# SOFTWEAR_microbit2.net
KiCad netlist of a schematic drawn in EAGLE
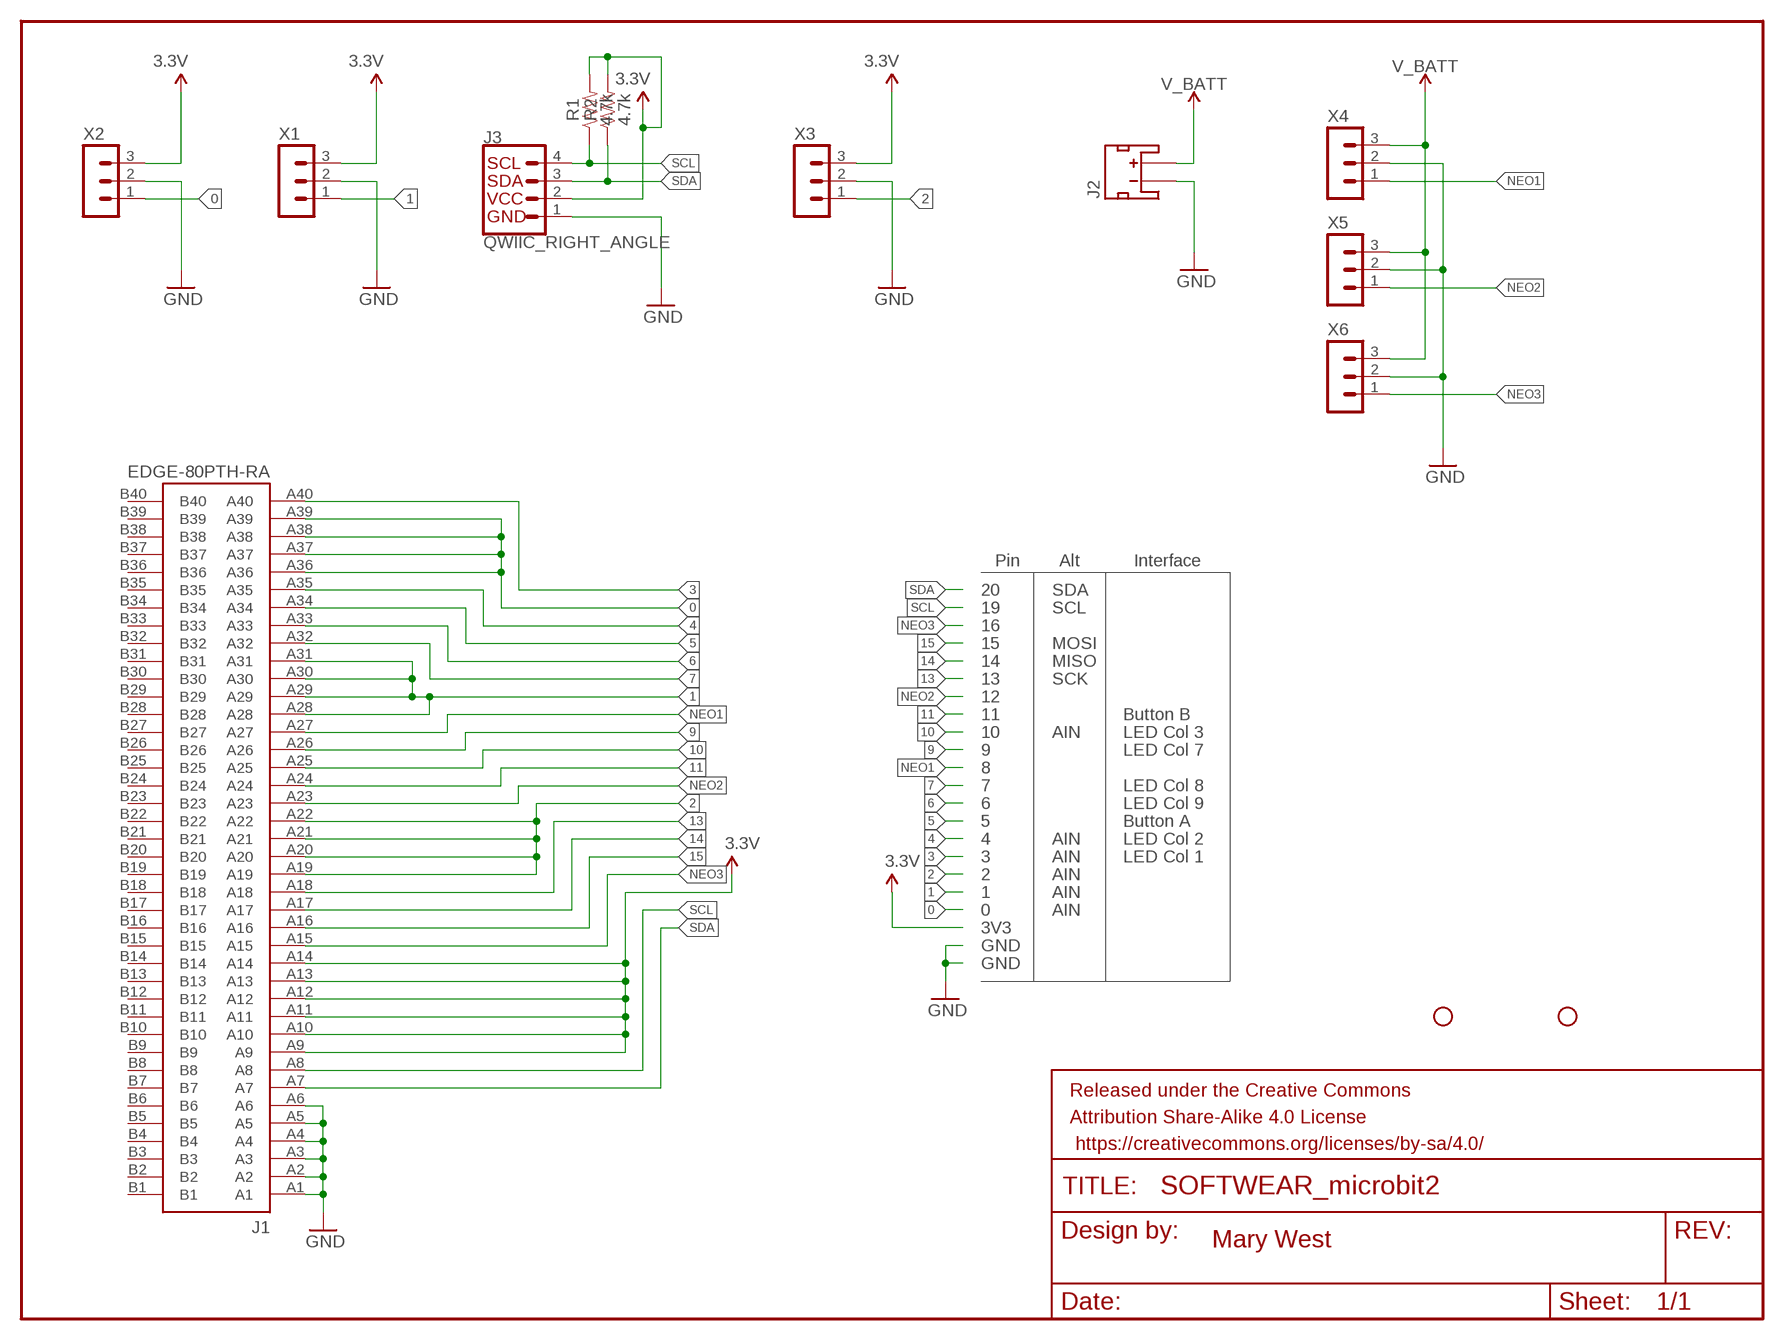
[diagram p0: schematic, sheet 1]

(export (version "E")
  (design (tool "Eeschema 10.0.6"))
  (components
    (comp (ref "FRAME2")
      (value "FRAME-LETTERNO_PACKAGE")
      (footprint "eagle-import:DUMMY")
      (fields (field (name "DESIGNER") "Nobody"))
      (libsource (lib "eagle-import") (part "FRAME-LETTERNO_PACKAGE"))
    )
    (comp (ref "H1")
      (value "STAND-OFF")
      (footprint "eagle-import:STAND-OFF")
      (libsource (lib "eagle-import") (part "STAND-OFF"))
    )
    (comp (ref "H2")
      (value "STAND-OFF")
      (footprint "eagle-import:STAND-OFF")
      (libsource (lib "eagle-import") (part "STAND-OFF"))
    )
    (comp (ref "J1")
      (value "EDGE-80PTH-RA")
      (footprint "eagle-import:VEC-127-080-R")
      (libsource (lib "eagle-import") (part "EDGE-80PTH-RA"))
    )
    (comp (ref "J2")
      (value "JST_2MM_MALE")
      (footprint "eagle-import:JST-2-SMD")
      (libsource (lib "eagle-import") (part "JST_2MM_MALE"))
    )
    (comp (ref "J3")
      (value "QWIIC_RIGHT_ANGLE")
      (footprint "eagle-import:JST04_1MM_RA")
      (libsource (lib "eagle-import") (part "QWIIC_CONNECTORJS-1MM"))
    )
    (comp (ref "R1")
      (value "4.7k")
      (footprint "eagle-import:0603")
      (libsource (lib "eagle-import") (part "4.7KOHM-0603-1/10W-1%"))
    )
    (comp (ref "R2")
      (value "4.7k")
      (footprint "eagle-import:0603")
      (libsource (lib "eagle-import") (part "4.7KOHM-0603-1/10W-1%"))
    )
    (comp (ref "X1")
      (value "SM03B-SRSS-TB")
      (footprint "eagle-import:SM03B-SRSS-TB")
      (libsource (lib "eagle-import") (part "SM03B-SRSS-TB"))
    )
    (comp (ref "X2")
      (value "SM03B-SRSS-TB")
      (footprint "eagle-import:SM03B-SRSS-TB")
      (libsource (lib "eagle-import") (part "SM03B-SRSS-TB"))
    )
    (comp (ref "X3")
      (value "SM03B-SRSS-TB")
      (footprint "eagle-import:SM03B-SRSS-TB")
      (libsource (lib "eagle-import") (part "SM03B-SRSS-TB"))
    )
    (comp (ref "X4")
      (value "SM03B-SRSS-TB")
      (footprint "eagle-import:SM03B-SRSS-TB")
      (libsource (lib "eagle-import") (part "SM03B-SRSS-TB"))
    )
    (comp (ref "X5")
      (value "SM03B-SRSS-TB")
      (footprint "eagle-import:SM03B-SRSS-TB")
      (libsource (lib "eagle-import") (part "SM03B-SRSS-TB"))
    )
    (comp (ref "X6")
      (value "SM03B-SRSS-TB")
      (footprint "eagle-import:SM03B-SRSS-TB")
      (libsource (lib "eagle-import") (part "SM03B-SRSS-TB"))
    )
  )
  (nets
    (net (code "1") (name "0") (class "Default")
      (node (ref "J1") (pin "A36") (pinfunction "A36_A36") (pintype "bidirectional"))
      (node (ref "J1") (pin "A37") (pinfunction "A37_A37") (pintype "bidirectional"))
      (node (ref "J1") (pin "A38") (pinfunction "A38_A38") (pintype "bidirectional"))
      (node (ref "J1") (pin "A39") (pinfunction "A39_A39") (pintype "bidirectional"))
      (node (ref "X2") (pin "1") (pinfunction "1_1") (pintype "passive"))
    )
    (net (code "2") (name "1") (class "Default")
      (node (ref "J1") (pin "A28") (pinfunction "A28_A28") (pintype "bidirectional"))
      (node (ref "J1") (pin "A29") (pinfunction "A29_A29") (pintype "bidirectional"))
      (node (ref "J1") (pin "A30") (pinfunction "A30_A30") (pintype "bidirectional"))
      (node (ref "J1") (pin "A31") (pinfunction "A31_A31") (pintype "bidirectional"))
      (node (ref "X1") (pin "1") (pinfunction "1_1") (pintype "passive"))
    )
    (net (code "3") (name "2") (class "Default")
      (node (ref "J1") (pin "A19") (pinfunction "A19_A19") (pintype "bidirectional"))
      (node (ref "J1") (pin "A20") (pinfunction "A20_A20") (pintype "bidirectional"))
      (node (ref "J1") (pin "A21") (pinfunction "A21_A21") (pintype "bidirectional"))
      (node (ref "J1") (pin "A22") (pinfunction "A22_A22") (pintype "bidirectional"))
      (node (ref "X3") (pin "1") (pinfunction "1_1") (pintype "passive"))
    )
    (net (code "4") (name "3") (class "Default")
      (node (ref "J1") (pin "A40") (pinfunction "A40_A40") (pintype "bidirectional"))
    )
    (net (code "5") (name "3.3V") (class "Default")
      (node (ref "J1") (pin "A10") (pinfunction "A10_A10") (pintype "bidirectional"))
      (node (ref "J1") (pin "A11") (pinfunction "A11_A11") (pintype "bidirectional"))
      (node (ref "J1") (pin "A12") (pinfunction "A12_A12") (pintype "bidirectional"))
      (node (ref "J1") (pin "A13") (pinfunction "A13_A13") (pintype "bidirectional"))
      (node (ref "J1") (pin "A14") (pinfunction "A14_A14") (pintype "bidirectional"))
      (node (ref "J1") (pin "A9") (pinfunction "A9_A9") (pintype "bidirectional"))
      (node (ref "J3") (pin "2") (pinfunction "2_2") (pintype "power_in"))
      (node (ref "R1") (pin "2") (pinfunction "2_2") (pintype "passive"))
      (node (ref "R2") (pin "2") (pinfunction "2_2") (pintype "passive"))
      (node (ref "X1") (pin "3") (pinfunction "3_3") (pintype "passive"))
      (node (ref "X2") (pin "3") (pinfunction "3_3") (pintype "passive"))
      (node (ref "X3") (pin "3") (pinfunction "3_3") (pintype "passive"))
    )
    (net (code "6") (name "4") (class "Default")
      (node (ref "J1") (pin "A35") (pinfunction "A35_A35") (pintype "bidirectional"))
    )
    (net (code "7") (name "5") (class "Default")
      (node (ref "J1") (pin "A34") (pinfunction "A34_A34") (pintype "bidirectional"))
    )
    (net (code "8") (name "6") (class "Default")
      (node (ref "J1") (pin "A33") (pinfunction "A33_A33") (pintype "bidirectional"))
    )
    (net (code "9") (name "7") (class "Default")
      (node (ref "J1") (pin "A32") (pinfunction "A32_A32") (pintype "bidirectional"))
    )
    (net (code "10") (name "9") (class "Default")
      (node (ref "J1") (pin "A26") (pinfunction "A26_A26") (pintype "bidirectional"))
    )
    (net (code "11") (name "10") (class "Default")
      (node (ref "J1") (pin "A25") (pinfunction "A25_A25") (pintype "bidirectional"))
    )
    (net (code "12") (name "11") (class "Default")
      (node (ref "J1") (pin "A24") (pinfunction "A24_A24") (pintype "bidirectional"))
    )
    (net (code "13") (name "13") (class "Default")
      (node (ref "J1") (pin "A18") (pinfunction "A18_A18") (pintype "bidirectional"))
    )
    (net (code "14") (name "14") (class "Default")
      (node (ref "J1") (pin "A17") (pinfunction "A17_A17") (pintype "bidirectional"))
    )
    (net (code "15") (name "15") (class "Default")
      (node (ref "J1") (pin "A16") (pinfunction "A16_A16") (pintype "bidirectional"))
    )
    (net (code "16") (name "GND") (class "Default")
      (node (ref "J1") (pin "A1") (pinfunction "A1_A1") (pintype "bidirectional"))
      (node (ref "J1") (pin "A2") (pinfunction "A2_A2") (pintype "bidirectional"))
      (node (ref "J1") (pin "A3") (pinfunction "A3_A3") (pintype "bidirectional"))
      (node (ref "J1") (pin "A4") (pinfunction "A4_A4") (pintype "bidirectional"))
      (node (ref "J1") (pin "A5") (pinfunction "A5_A5") (pintype "bidirectional"))
      (node (ref "J1") (pin "A6") (pinfunction "A6_A6") (pintype "bidirectional"))
      (node (ref "J2") (pin "1") (pinfunction "-_1") (pintype "bidirectional"))
      (node (ref "J3") (pin "1") (pinfunction "1_1") (pintype "power_in"))
      (node (ref "X1") (pin "2") (pinfunction "2_2") (pintype "passive"))
      (node (ref "X2") (pin "2") (pinfunction "2_2") (pintype "passive"))
      (node (ref "X3") (pin "2") (pinfunction "2_2") (pintype "passive"))
      (node (ref "X4") (pin "2") (pinfunction "2_2") (pintype "passive"))
      (node (ref "X5") (pin "2") (pinfunction "2_2") (pintype "passive"))
      (node (ref "X6") (pin "2") (pinfunction "2_2") (pintype "passive"))
    )
    (net (code "17") (name "NEO1") (class "Default")
      (node (ref "J1") (pin "A27") (pinfunction "A27_A27") (pintype "bidirectional"))
      (node (ref "X4") (pin "1") (pinfunction "1_1") (pintype "passive"))
    )
    (net (code "18") (name "NEO2") (class "Default")
      (node (ref "J1") (pin "A23") (pinfunction "A23_A23") (pintype "bidirectional"))
      (node (ref "X5") (pin "1") (pinfunction "1_1") (pintype "passive"))
    )
    (net (code "19") (name "NEO3") (class "Default")
      (node (ref "J1") (pin "A15") (pinfunction "A15_A15") (pintype "bidirectional"))
      (node (ref "X6") (pin "1") (pinfunction "1_1") (pintype "passive"))
    )
    (net (code "20") (name "SCL") (class "Default")
      (node (ref "J1") (pin "A8") (pinfunction "A8_A8") (pintype "bidirectional"))
      (node (ref "J3") (pin "4") (pinfunction "4_4") (pintype "passive"))
      (node (ref "R1") (pin "1") (pinfunction "1_1") (pintype "passive"))
    )
    (net (code "21") (name "SDA") (class "Default")
      (node (ref "J1") (pin "A7") (pinfunction "A7_A7") (pintype "bidirectional"))
      (node (ref "J3") (pin "3") (pinfunction "3_3") (pintype "passive"))
      (node (ref "R2") (pin "1") (pinfunction "1_1") (pintype "passive"))
    )
    (net (code "22") (name "V_BATT") (class "Default")
      (node (ref "J2") (pin "2") (pinfunction "+_2") (pintype "bidirectional"))
      (node (ref "X4") (pin "3") (pinfunction "3_3") (pintype "passive"))
      (node (ref "X5") (pin "3") (pinfunction "3_3") (pintype "passive"))
      (node (ref "X6") (pin "3") (pinfunction "3_3") (pintype "passive"))
    )
    (net (code "23") (name "unconnected-(J1-PadB1)") (class "Default")
      (node (ref "J1") (pin "B1") (pinfunction "B1_B1") (pintype "bidirectional"))
    )
    (net (code "24") (name "unconnected-(J1-PadB2)") (class "Default")
      (node (ref "J1") (pin "B2") (pinfunction "B2_B2") (pintype "bidirectional"))
    )
    (net (code "25") (name "unconnected-(J1-PadB3)") (class "Default")
      (node (ref "J1") (pin "B3") (pinfunction "B3_B3") (pintype "bidirectional"))
    )
    (net (code "26") (name "unconnected-(J1-PadB4)") (class "Default")
      (node (ref "J1") (pin "B4") (pinfunction "B4_B4") (pintype "bidirectional"))
    )
    (net (code "27") (name "unconnected-(J1-PadB5)") (class "Default")
      (node (ref "J1") (pin "B5") (pinfunction "B5_B5") (pintype "bidirectional"))
    )
    (net (code "28") (name "unconnected-(J1-PadB6)") (class "Default")
      (node (ref "J1") (pin "B6") (pinfunction "B6_B6") (pintype "bidirectional"))
    )
    (net (code "29") (name "unconnected-(J1-PadB7)") (class "Default")
      (node (ref "J1") (pin "B7") (pinfunction "B7_B7") (pintype "bidirectional"))
    )
    (net (code "30") (name "unconnected-(J1-PadB8)") (class "Default")
      (node (ref "J1") (pin "B8") (pinfunction "B8_B8") (pintype "bidirectional"))
    )
    (net (code "31") (name "unconnected-(J1-PadB9)") (class "Default")
      (node (ref "J1") (pin "B9") (pinfunction "B9_B9") (pintype "bidirectional"))
    )
    (net (code "32") (name "unconnected-(J1-PadB10)") (class "Default")
      (node (ref "J1") (pin "B10") (pinfunction "B10_B10") (pintype "bidirectional"))
    )
    (net (code "33") (name "unconnected-(J1-PadB11)") (class "Default")
      (node (ref "J1") (pin "B11") (pinfunction "B11_B11") (pintype "bidirectional"))
    )
    (net (code "34") (name "unconnected-(J1-PadB12)") (class "Default")
      (node (ref "J1") (pin "B12") (pinfunction "B12_B12") (pintype "bidirectional"))
    )
    (net (code "35") (name "unconnected-(J1-PadB13)") (class "Default")
      (node (ref "J1") (pin "B13") (pinfunction "B13_B13") (pintype "bidirectional"))
    )
    (net (code "36") (name "unconnected-(J1-PadB14)") (class "Default")
      (node (ref "J1") (pin "B14") (pinfunction "B14_B14") (pintype "bidirectional"))
    )
    (net (code "37") (name "unconnected-(J1-PadB15)") (class "Default")
      (node (ref "J1") (pin "B15") (pinfunction "B15_B15") (pintype "bidirectional"))
    )
    (net (code "38") (name "unconnected-(J1-PadB16)") (class "Default")
      (node (ref "J1") (pin "B16") (pinfunction "B16_B16") (pintype "bidirectional"))
    )
    (net (code "39") (name "unconnected-(J1-PadB17)") (class "Default")
      (node (ref "J1") (pin "B17") (pinfunction "B17_B17") (pintype "bidirectional"))
    )
    (net (code "40") (name "unconnected-(J1-PadB18)") (class "Default")
      (node (ref "J1") (pin "B18") (pinfunction "B18_B18") (pintype "bidirectional"))
    )
    (net (code "41") (name "unconnected-(J1-PadB19)") (class "Default")
      (node (ref "J1") (pin "B19") (pinfunction "B19_B19") (pintype "bidirectional"))
    )
    (net (code "42") (name "unconnected-(J1-PadB20)") (class "Default")
      (node (ref "J1") (pin "B20") (pinfunction "B20_B20") (pintype "bidirectional"))
    )
    (net (code "43") (name "unconnected-(J1-PadB21)") (class "Default")
      (node (ref "J1") (pin "B21") (pinfunction "B21_B21") (pintype "bidirectional"))
    )
    (net (code "44") (name "unconnected-(J1-PadB22)") (class "Default")
      (node (ref "J1") (pin "B22") (pinfunction "B22_B22") (pintype "bidirectional"))
    )
    (net (code "45") (name "unconnected-(J1-PadB23)") (class "Default")
      (node (ref "J1") (pin "B23") (pinfunction "B23_B23") (pintype "bidirectional"))
    )
    (net (code "46") (name "unconnected-(J1-PadB24)") (class "Default")
      (node (ref "J1") (pin "B24") (pinfunction "B24_B24") (pintype "bidirectional"))
    )
    (net (code "47") (name "unconnected-(J1-PadB25)") (class "Default")
      (node (ref "J1") (pin "B25") (pinfunction "B25_B25") (pintype "bidirectional"))
    )
    (net (code "48") (name "unconnected-(J1-PadB26)") (class "Default")
      (node (ref "J1") (pin "B26") (pinfunction "B26_B26") (pintype "bidirectional"))
    )
    (net (code "49") (name "unconnected-(J1-PadB27)") (class "Default")
      (node (ref "J1") (pin "B27") (pinfunction "B27_B27") (pintype "bidirectional"))
    )
    (net (code "50") (name "unconnected-(J1-PadB28)") (class "Default")
      (node (ref "J1") (pin "B28") (pinfunction "B28_B28") (pintype "bidirectional"))
    )
    (net (code "51") (name "unconnected-(J1-PadB29)") (class "Default")
      (node (ref "J1") (pin "B29") (pinfunction "B29_B29") (pintype "bidirectional"))
    )
    (net (code "52") (name "unconnected-(J1-PadB30)") (class "Default")
      (node (ref "J1") (pin "B30") (pinfunction "B30_B30") (pintype "bidirectional"))
    )
    (net (code "53") (name "unconnected-(J1-PadB31)") (class "Default")
      (node (ref "J1") (pin "B31") (pinfunction "B31_B31") (pintype "bidirectional"))
    )
    (net (code "54") (name "unconnected-(J1-PadB32)") (class "Default")
      (node (ref "J1") (pin "B32") (pinfunction "B32_B32") (pintype "bidirectional"))
    )
    (net (code "55") (name "unconnected-(J1-PadB33)") (class "Default")
      (node (ref "J1") (pin "B33") (pinfunction "B33_B33") (pintype "bidirectional"))
    )
    (net (code "56") (name "unconnected-(J1-PadB34)") (class "Default")
      (node (ref "J1") (pin "B34") (pinfunction "B34_B34") (pintype "bidirectional"))
    )
    (net (code "57") (name "unconnected-(J1-PadB35)") (class "Default")
      (node (ref "J1") (pin "B35") (pinfunction "B35_B35") (pintype "bidirectional"))
    )
    (net (code "58") (name "unconnected-(J1-PadB36)") (class "Default")
      (node (ref "J1") (pin "B36") (pinfunction "B36_B36") (pintype "bidirectional"))
    )
    (net (code "59") (name "unconnected-(J1-PadB37)") (class "Default")
      (node (ref "J1") (pin "B37") (pinfunction "B37_B37") (pintype "bidirectional"))
    )
    (net (code "60") (name "unconnected-(J1-PadB38)") (class "Default")
      (node (ref "J1") (pin "B38") (pinfunction "B38_B38") (pintype "bidirectional"))
    )
    (net (code "61") (name "unconnected-(J1-PadB39)") (class "Default")
      (node (ref "J1") (pin "B39") (pinfunction "B39_B39") (pintype "bidirectional"))
    )
    (net (code "62") (name "unconnected-(J1-PadB40)") (class "Default")
      (node (ref "J1") (pin "B40") (pinfunction "B40_B40") (pintype "bidirectional"))
    )
    (net (code "63") (name "unconnected-(J2-PAD1-PadNC1)") (class "Default")
      (node (ref "J2") (pin "NC1") (pinfunction "PAD1_NC1") (pintype "bidirectional"))
    )
    (net (code "64") (name "unconnected-(J2-PAD2-PadNC2)") (class "Default")
      (node (ref "J2") (pin "NC2") (pinfunction "PAD2_NC2") (pintype "bidirectional"))
    )
  )
)
